# TX.net
KiCad netlist of a schematic drawn in Altium Designer
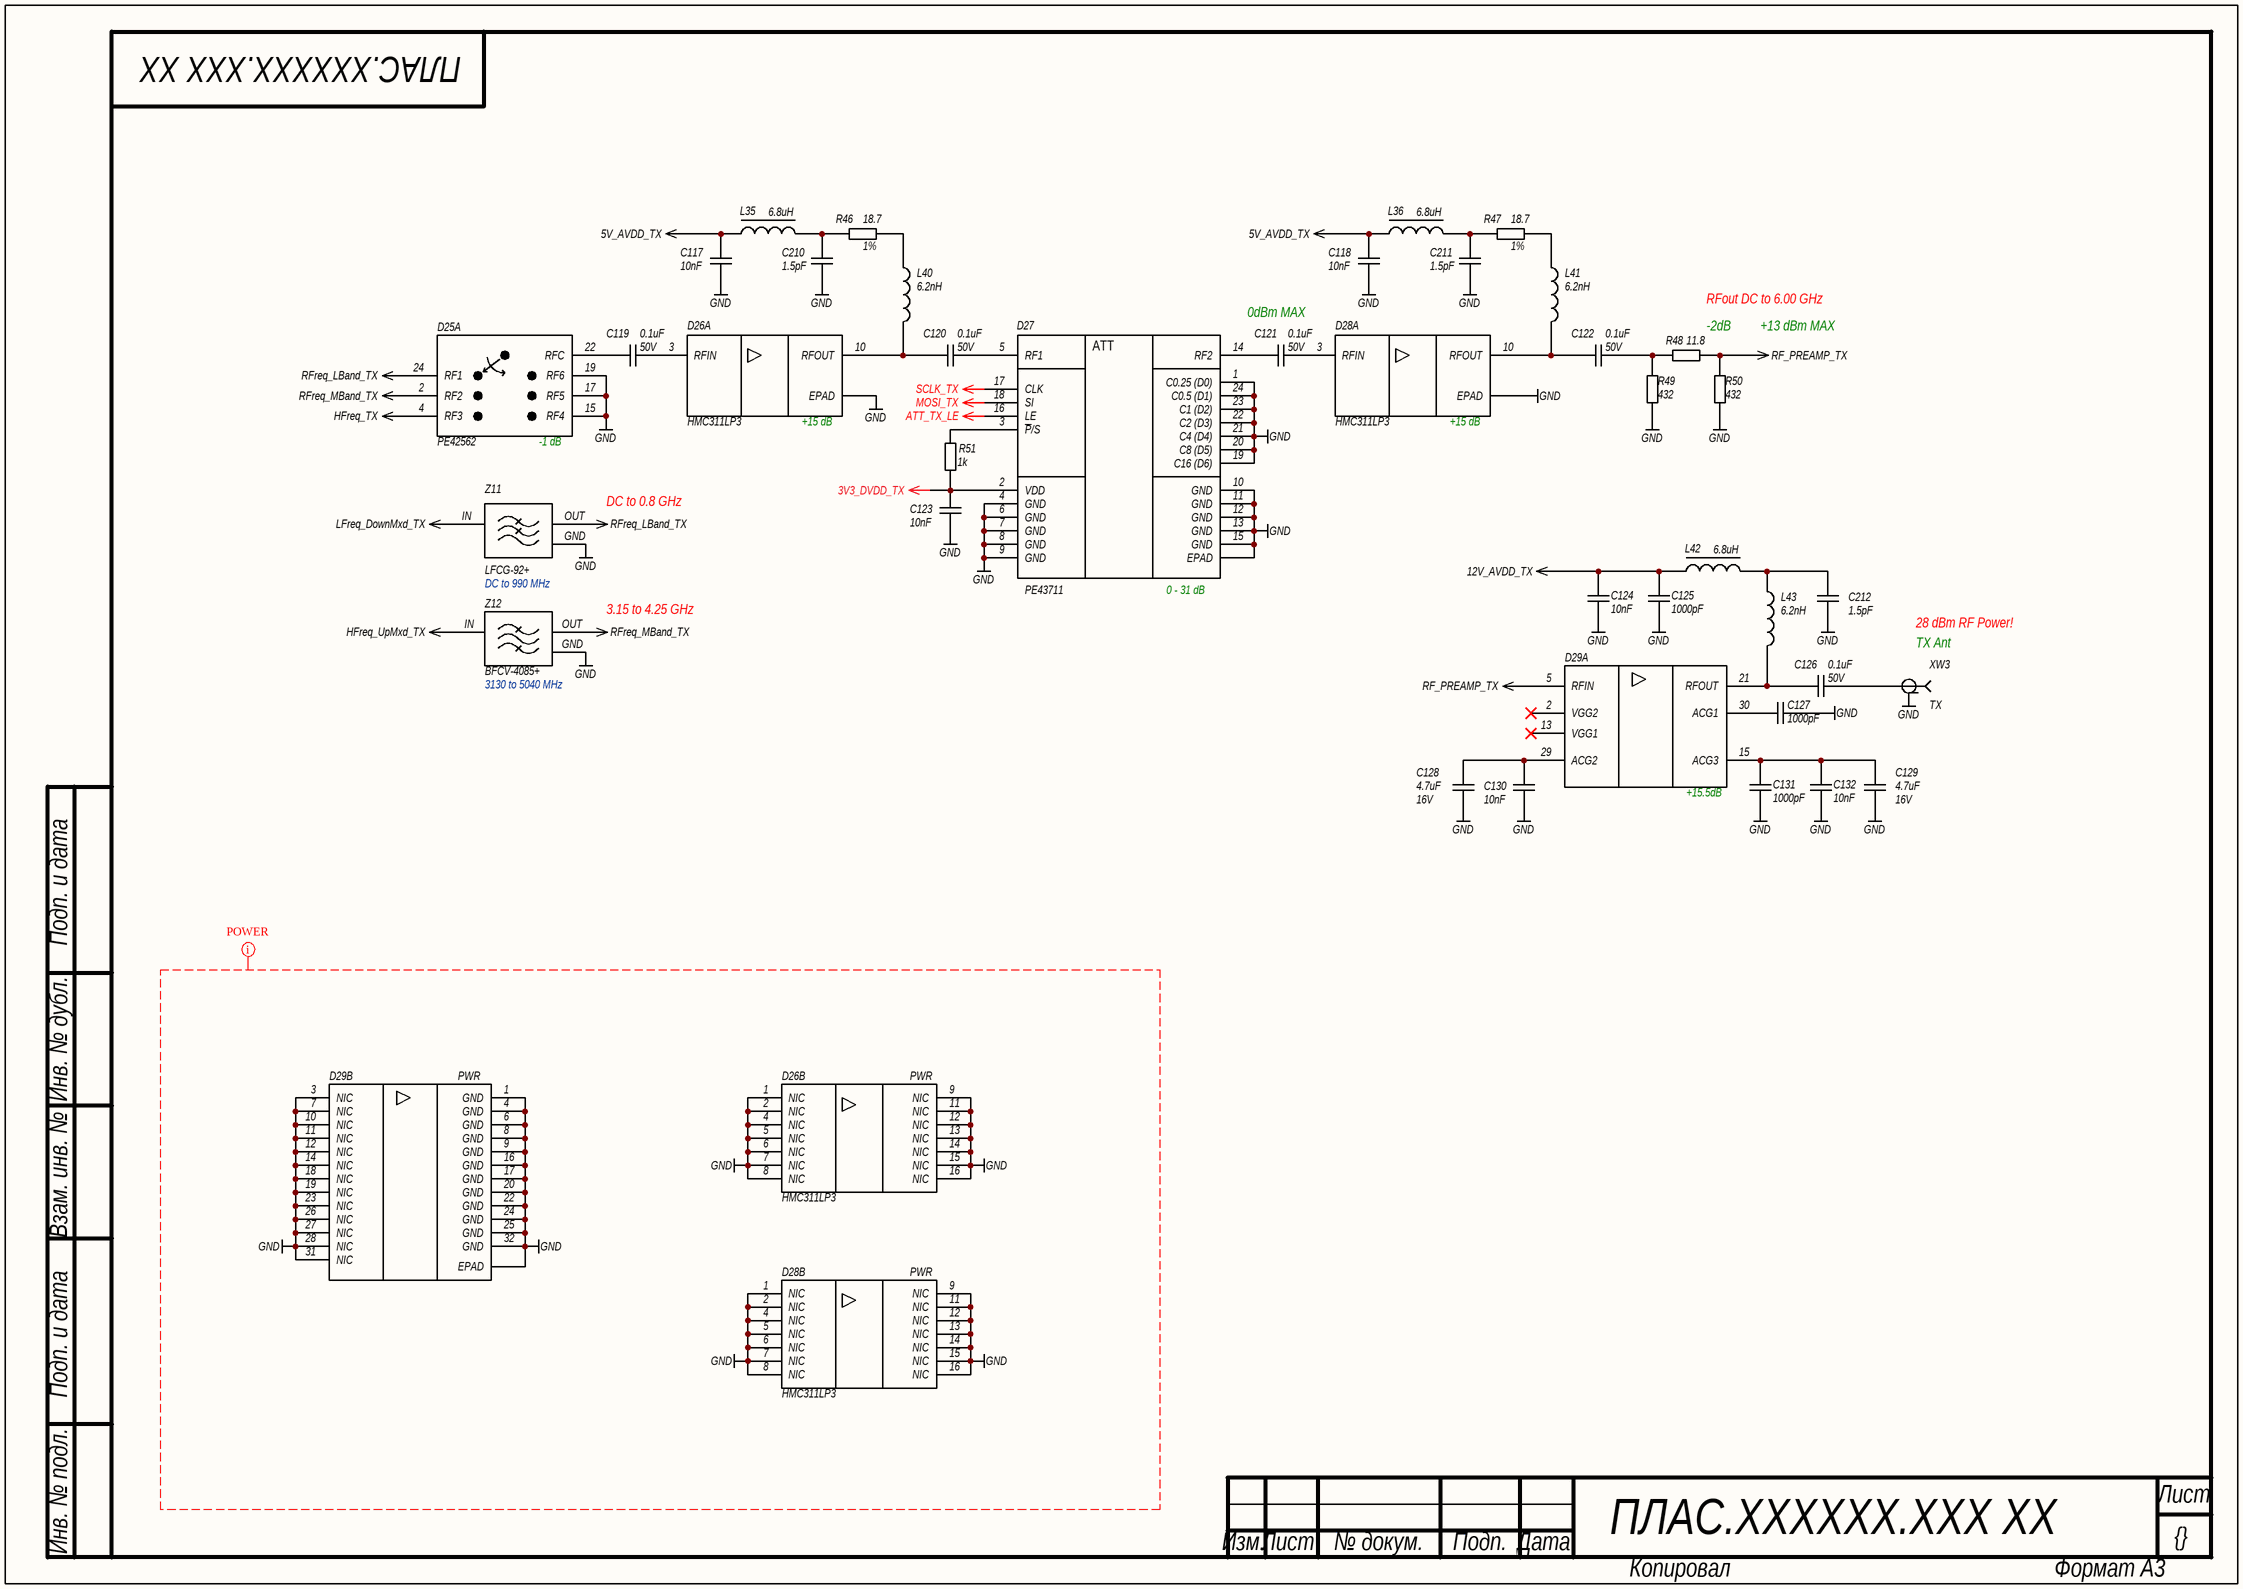
[diagram p0: TX.SchDoc]

(export (version "E")
  (design (tool "Eeschema 10.0.6"))
  (components
    (comp (ref "C117")
      (value "10nF")
      (footprint "C0402")
      (description "SMD Capacitor")
      (fields (field (name "MANUFACTURER") "Murata") (field (name "TOLERANCE") "10%"))
      (libsource (lib "Kintex_SDR") (part "CAP"))
    )
    (comp (ref "C118")
      (value "10nF")
      (footprint "C0402")
      (description "SMD Capacitor")
      (fields (field (name "MANUFACTURER") "Murata") (field (name "TOLERANCE") "10%"))
      (libsource (lib "Kintex_SDR") (part "CAP"))
    )
    (comp (ref "C119")
      (value "0.1uF")
      (footprint "C1206")
      (description "SMD Capacitor")
      (fields
        (field (name "MANUFACTURER") "Murata")
        (field (name "TOLERANCE") "5%")
        (field (name "VOLTAGE") "50V")
      )
      (libsource (lib "Kintex_SDR") (part "CAP"))
    )
    (comp (ref "C120")
      (value "0.1uF")
      (footprint "C1206")
      (description "SMD Capacitor")
      (fields
        (field (name "MANUFACTURER") "Murata")
        (field (name "TOLERANCE") "5%")
        (field (name "VOLTAGE") "50V")
      )
      (libsource (lib "Kintex_SDR") (part "CAP"))
    )
    (comp (ref "C121")
      (value "0.1uF")
      (footprint "C1206")
      (description "SMD Capacitor")
      (fields
        (field (name "MANUFACTURER") "Murata")
        (field (name "TOLERANCE") "5%")
        (field (name "VOLTAGE") "50V")
      )
      (libsource (lib "Kintex_SDR") (part "CAP"))
    )
    (comp (ref "C122")
      (value "0.1uF")
      (footprint "C1206")
      (description "SMD Capacitor")
      (fields
        (field (name "MANUFACTURER") "Murata")
        (field (name "TOLERANCE") "5%")
        (field (name "VOLTAGE") "50V")
      )
      (libsource (lib "Kintex_SDR") (part "CAP"))
    )
    (comp (ref "C123")
      (value "10nF")
      (footprint "C0402")
      (description "SMD Capacitor")
      (fields (field (name "MANUFACTURER") "Murata") (field (name "TOLERANCE") "10%"))
      (libsource (lib "Kintex_SDR") (part "CAP"))
    )
    (comp (ref "C124")
      (value "10nF")
      (footprint "C0402")
      (description "SMD Capacitor")
      (fields (field (name "MANUFACTURER") "Murata") (field (name "TOLERANCE") "10%"))
      (libsource (lib "Kintex_SDR") (part "CAP"))
    )
    (comp (ref "C125")
      (value "1000pF")
      (footprint "C0402")
      (description "SMD Capacitor")
      (fields (field (name "MANUFACTURER") "Murata") (field (name "TOLERANCE") "5%"))
      (libsource (lib "Kintex_SDR") (part "CAP"))
    )
    (comp (ref "C126")
      (value "0.1uF")
      (footprint "C1206")
      (description "SMD Capacitor")
      (fields
        (field (name "MANUFACTURER") "Murata")
        (field (name "TOLERANCE") "5%")
        (field (name "VOLTAGE") "50V")
      )
      (libsource (lib "Kintex_SDR") (part "CAP"))
    )
    (comp (ref "C127")
      (value "1000pF")
      (footprint "C0402")
      (description "SMD Capacitor")
      (fields (field (name "MANUFACTURER") "Murata") (field (name "TOLERANCE") "5%"))
      (libsource (lib "Kintex_SDR") (part "CAP"))
    )
    (comp (ref "C128")
      (value "4.7uF")
      (footprint "C0603")
      (description "SMD Capacitor")
      (fields
        (field (name "MANUFACTURER") "Murata")
        (field (name "TOLERANCE") "10%")
        (field (name "VOLTAGE") "16V")
      )
      (libsource (lib "Kintex_SDR") (part "CAP"))
    )
    (comp (ref "C129")
      (value "4.7uF")
      (footprint "C0603")
      (description "SMD Capacitor")
      (fields
        (field (name "MANUFACTURER") "Murata")
        (field (name "TOLERANCE") "10%")
        (field (name "VOLTAGE") "16V")
      )
      (libsource (lib "Kintex_SDR") (part "CAP"))
    )
    (comp (ref "C130")
      (value "10nF")
      (footprint "C0402")
      (description "SMD Capacitor")
      (fields (field (name "MANUFACTURER") "Murata") (field (name "TOLERANCE") "10%"))
      (libsource (lib "Kintex_SDR") (part "CAP"))
    )
    (comp (ref "C131")
      (value "1000pF")
      (footprint "C0402")
      (description "SMD Capacitor")
      (fields (field (name "MANUFACTURER") "Murata") (field (name "TOLERANCE") "5%"))
      (libsource (lib "Kintex_SDR") (part "CAP"))
    )
    (comp (ref "C132")
      (value "10nF")
      (footprint "C0402")
      (description "SMD Capacitor")
      (fields (field (name "MANUFACTURER") "Murata") (field (name "TOLERANCE") "10%"))
      (libsource (lib "Kintex_SDR") (part "CAP"))
    )
    (comp (ref "C210")
      (value "1.5pF")
      (footprint "C0402")
      (description "SMD Capacitor")
      (fields (field (name "MANUFACTURER") "Murata") (field (name "TOLERANCE") "±0.05pF"))
      (libsource (lib "Kintex_SDR") (part "CAP"))
    )
    (comp (ref "C211")
      (value "1.5pF")
      (footprint "C0402")
      (description "SMD Capacitor")
      (fields (field (name "MANUFACTURER") "Murata") (field (name "TOLERANCE") "±0.05pF"))
      (libsource (lib "Kintex_SDR") (part "CAP"))
    )
    (comp (ref "C212")
      (value "1.5pF")
      (footprint "C0402")
      (description "SMD Capacitor")
      (fields (field (name "MANUFACTURER") "Murata") (field (name "TOLERANCE") "±0.05pF"))
      (libsource (lib "Kintex_SDR") (part "CAP"))
    )
    (comp (ref "D25")
      (value "PE42562")
      (footprint "QFN-24")
      (description "The PE42582 is a HaRP™ technology-enhanced absorptive SP6T RF switch")
      (fields (field (name "MANUFACTURER") "Peregrine Technical Solutions"))
      (libsource (lib "DBLib") (part "PE42562"))
    )
    (comp (ref "D26")
      (value "HMC311LP3")
      (footprint "DBLib:QFN-16 v2")
      (description "InGaP HBT GAIN BLOCK")
      (fields (field (name "MANUFACTURER") "Analog Devices"))
      (libsource (lib "DBLib") (part "HMC311LP3"))
    )
    (comp (ref "D27")
      (value "PE43711")
      (footprint "QFN-24")
      (description "The PE43711 is a 50Ω, HaRP™ technology-enhanced, 7-bit RF digital step attenuator")
      (fields (field (name "MANUFACTURER") "Peregrine Technical Solutions"))
      (libsource (lib "DBLib") (part "PE43711"))
    )
    (comp (ref "D28")
      (value "HMC311LP3")
      (footprint "DBLib:QFN-16 v2")
      (description "InGaP HBT GAIN BLOCK")
      (fields (field (name "MANUFACTURER") "Analog Devices"))
      (libsource (lib "DBLib") (part "HMC311LP3"))
    )
    (comp (ref "D29")
      (value "HMC637BPM5E")
      (footprint "DBLib:LFCSP-32")
      (description "1 W Power Amplifier")
      (fields
        (field (name "MANUFACTURER") "Analog Devices")
        (field (name "VOLTAGE") "12 V at 345 mA typical")
      )
      (libsource (lib "DBLib") (part "HMC637BPM5E"))
    )
    (comp (ref "L35")
      (value "6.8uH")
      (footprint "DBLib:XFL3012")
      (description "Chip SMD Inductor")
      (fields (field (name "MANUFACTURER") "Coilcraft") (field (name "TOLERANCE") "±5%"))
      (libsource (lib "DBLib") (part "Inductor"))
    )
    (comp (ref "L36")
      (value "6.8uH")
      (footprint "DBLib:XFL3012")
      (description "Chip SMD Inductor")
      (fields (field (name "MANUFACTURER") "Coilcraft") (field (name "TOLERANCE") "±5%"))
      (libsource (lib "DBLib") (part "Inductor"))
    )
    (comp (ref "L40")
      (value "6.2nH")
      (footprint "DBLib:L0805_HP")
      (description "Chip SMD Inductor")
      (fields (field (name "MANUFACTURER") "Coilcraft") (field (name "TOLERANCE") "5%"))
      (libsource (lib "DBLib") (part "Inductor RF"))
    )
    (comp (ref "L41")
      (value "6.2nH")
      (footprint "DBLib:L0805_HP")
      (description "Chip SMD Inductor")
      (fields (field (name "MANUFACTURER") "Coilcraft") (field (name "TOLERANCE") "5%"))
      (libsource (lib "DBLib") (part "Inductor RF"))
    )
    (comp (ref "L42")
      (value "6.8uH")
      (footprint "DBLib:XFL3012")
      (description "Chip SMD Inductor")
      (fields (field (name "MANUFACTURER") "Coilcraft") (field (name "TOLERANCE") "±5%"))
      (libsource (lib "DBLib") (part "Inductor"))
    )
    (comp (ref "L43")
      (value "6.2nH")
      (footprint "DBLib:L0805_HP")
      (description "Chip SMD Inductor")
      (fields (field (name "MANUFACTURER") "Coilcraft") (field (name "TOLERANCE") "5%"))
      (libsource (lib "DBLib") (part "Inductor RF"))
    )
    (comp (ref "R46")
      (value "18.7")
      (footprint "R0805")
      (description "SMD Resistor")
      (fields
        (field (name "POWER") "0.125 Wt")
        (field (name "TOLERANCE") "1%")
        (field (name "MANUFACTURER") "Panasonic Electronic Components")
      )
      (libsource (lib "Kintex_SDR") (part "RES"))
    )
    (comp (ref "R47")
      (value "18.7")
      (footprint "R0805")
      (description "SMD Resistor")
      (fields
        (field (name "POWER") "0.125 Wt")
        (field (name "TOLERANCE") "1%")
        (field (name "MANUFACTURER") "Panasonic Electronic Components")
      )
      (libsource (lib "Kintex_SDR") (part "RES"))
    )
    (comp (ref "R48")
      (value "11.8")
      (footprint "R0402")
      (description "SMD Resistor")
      (fields (field (name "POWER") "0.063 Wt") (field (name "TOLERANCE") "±1%"))
      (libsource (lib "Kintex_SDR") (part "RES"))
    )
    (comp (ref "R49")
      (value "432")
      (footprint "R0402")
      (description "SMD Resistor")
      (fields (field (name "POWER") "0.1 Wt") (field (name "TOLERANCE") "±1%"))
      (libsource (lib "") (part "RES_1"))
    )
    (comp (ref "R50")
      (value "432")
      (footprint "R0402")
      (description "SMD Resistor")
      (fields (field (name "POWER") "0.1 Wt") (field (name "TOLERANCE") "±1%"))
      (libsource (lib "") (part "RES_1"))
    )
    (comp (ref "R51")
      (value "1k")
      (footprint "R0402")
      (description "SMD Resistor")
      (fields (field (name "POWER") "0.062 Wt") (field (name "TOLERANCE") "5%"))
      (libsource (lib "") (part "RES_2"))
    )
    (comp (ref "XW3")
      (value "TX")
      (footprint "MOLEX SD-73251-135 (Gold)")
      (description "50 Ohms, SMA Jack, Vertica")
      (fields (field (name "MANUFACTURER") "Molex"))
      (libsource (lib "DBLib") (part "RF Connector"))
    )
    (comp (ref "Z11")
      (value "LFCG-92+")
      (footprint "GE0805C-2")
      (description "Low Pass Filter")
      (fields (field (name "MANUFACTURER") "Mini-Circuits") (field (name "FREQUENCY") "DC to 990 MHz"))
      (libsource (lib "DBLib") (part "LFCG-92+"))
    )
    (comp (ref "Z12")
      (value "BFCV-4085+")
      (footprint "JV1210C")
      (description "Bandpass Filter")
      (fields (field (name "MANUFACTURER") "Mini-Circuits") (field (name "FREQUENCY") "3130 to 5040 MHz"))
      (libsource (lib "DBLib") (part "BFCV-4085+"))
    )
  )
  (nets
    (net (code "1") (name "3V3_DVDD_TX") (class "Default")
      (node (ref "C123") (pin "2") (pinfunction "2_2") (pintype "passive"))
      (node (ref "D27") (pin "2") (pinfunction "VDD_2") (pintype "passive"))
      (node (ref "R51") (pin "1") (pinfunction "1_1") (pintype "passive"))
    )
    (net (code "2") (name "5V_AVDD_TX") (class "Default")
      (node (ref "C117") (pin "2") (pinfunction "2_2") (pintype "passive"))
      (node (ref "C118") (pin "2") (pinfunction "2_2") (pintype "passive"))
      (node (ref "L35") (pin "1") (pinfunction "1_1") (pintype "passive"))
      (node (ref "L36") (pin "1") (pinfunction "1_1") (pintype "passive"))
    )
    (net (code "3") (name "12V_AVDD_TX") (class "Default")
      (node (ref "C124") (pin "2") (pinfunction "2_2") (pintype "passive"))
      (node (ref "C125") (pin "2") (pinfunction "2_2") (pintype "passive"))
      (node (ref "L42") (pin "1") (pinfunction "1_1") (pintype "passive"))
    )
    (net (code "4") (name "ATT_TX_LE") (class "Default")
      (node (ref "D27") (pin "16") (pinfunction "LE_16") (pintype "passive"))
    )
    (net (code "5") (name "GND") (class "Default")
      (node (ref "C117") (pin "1") (pinfunction "1_1") (pintype "passive"))
      (node (ref "C118") (pin "1") (pinfunction "1_1") (pintype "passive"))
      (node (ref "C123") (pin "1") (pinfunction "1_1") (pintype "passive"))
      (node (ref "C124") (pin "1") (pinfunction "1_1") (pintype "passive"))
      (node (ref "C125") (pin "1") (pinfunction "1_1") (pintype "passive"))
      (node (ref "C127") (pin "2") (pinfunction "2_2") (pintype "passive"))
      (node (ref "C128") (pin "2") (pinfunction "2_2") (pintype "passive"))
      (node (ref "C129") (pin "2") (pinfunction "2_2") (pintype "passive"))
      (node (ref "C130") (pin "1") (pinfunction "1_1") (pintype "passive"))
      (node (ref "C131") (pin "1") (pinfunction "1_1") (pintype "passive"))
      (node (ref "C132") (pin "1") (pinfunction "1_1") (pintype "passive"))
      (node (ref "C210") (pin "1") (pinfunction "1_1") (pintype "passive"))
      (node (ref "C211") (pin "1") (pinfunction "1_1") (pintype "passive"))
      (node (ref "C212") (pin "1") (pinfunction "1_1") (pintype "passive"))
      (node (ref "D25") (pin "15") (pinfunction "RF4_15") (pintype "passive"))
      (node (ref "D25") (pin "17") (pinfunction "RF5_17") (pintype "passive"))
      (node (ref "D25") (pin "19") (pinfunction "RF6_19") (pintype "passive"))
      (node (ref "D26") (pin "1") (pinfunction "NIC_1") (pintype "passive"))
      (node (ref "D26") (pin "11") (pinfunction "NIC_11") (pintype "passive"))
      (node (ref "D26") (pin "12") (pinfunction "NIC_12") (pintype "passive"))
      (node (ref "D26") (pin "13") (pinfunction "NIC_13") (pintype "passive"))
      (node (ref "D26") (pin "14") (pinfunction "NIC_14") (pintype "passive"))
      (node (ref "D26") (pin "15") (pinfunction "NIC_15") (pintype "passive"))
      (node (ref "D26") (pin "16") (pinfunction "NIC_16") (pintype "passive"))
      (node (ref "D26") (pin "17") (pinfunction "EPAD_17") (pintype "passive"))
      (node (ref "D26") (pin "2") (pinfunction "NIC_2") (pintype "passive"))
      (node (ref "D26") (pin "4") (pinfunction "NIC_4") (pintype "passive"))
      (node (ref "D26") (pin "5") (pinfunction "NIC_5") (pintype "passive"))
      (node (ref "D26") (pin "6") (pinfunction "NIC_6") (pintype "passive"))
      (node (ref "D26") (pin "7") (pinfunction "NIC_7") (pintype "passive"))
      (node (ref "D26") (pin "8") (pinfunction "NIC_8") (pintype "passive"))
      (node (ref "D26") (pin "9") (pinfunction "NIC_9") (pintype "passive"))
      (node (ref "D27") (pin "1") (pinfunction "C0.25_(D0)_1") (pintype "passive"))
      (node (ref "D27") (pin "10") (pinfunction "GND_10") (pintype "passive"))
      (node (ref "D27") (pin "11") (pinfunction "GND_11") (pintype "passive"))
      (node (ref "D27") (pin "12") (pinfunction "GND_12") (pintype "passive"))
      (node (ref "D27") (pin "13") (pinfunction "GND_13") (pintype "passive"))
      (node (ref "D27") (pin "15") (pinfunction "GND_15") (pintype "passive"))
      (node (ref "D27") (pin "19") (pinfunction "C16_(D6)_19") (pintype "passive"))
      (node (ref "D27") (pin "20") (pinfunction "C8_(D5)_20") (pintype "passive"))
      (node (ref "D27") (pin "21") (pinfunction "C4_(D4)_21") (pintype "passive"))
      (node (ref "D27") (pin "22") (pinfunction "C2_(D3)_22") (pintype "passive"))
      (node (ref "D27") (pin "23") (pinfunction "C1_(D2)_23") (pintype "passive"))
      (node (ref "D27") (pin "24") (pinfunction "C0.5_(D1)_24") (pintype "passive"))
      (node (ref "D27") (pin "25") (pinfunction "EPAD_25") (pintype "passive"))
      (node (ref "D27") (pin "4") (pinfunction "GND_4") (pintype "passive"))
      (node (ref "D27") (pin "6") (pinfunction "GND_6") (pintype "passive"))
      (node (ref "D27") (pin "7") (pinfunction "GND_7") (pintype "passive"))
      (node (ref "D27") (pin "8") (pinfunction "GND_8") (pintype "passive"))
      (node (ref "D27") (pin "9") (pinfunction "GND_9") (pintype "passive"))
      (node (ref "D28") (pin "1") (pinfunction "NIC_1") (pintype "passive"))
      (node (ref "D28") (pin "11") (pinfunction "NIC_11") (pintype "passive"))
      (node (ref "D28") (pin "12") (pinfunction "NIC_12") (pintype "passive"))
      (node (ref "D28") (pin "13") (pinfunction "NIC_13") (pintype "passive"))
      (node (ref "D28") (pin "14") (pinfunction "NIC_14") (pintype "passive"))
      (node (ref "D28") (pin "15") (pinfunction "NIC_15") (pintype "passive"))
      (node (ref "D28") (pin "16") (pinfunction "NIC_16") (pintype "passive"))
      (node (ref "D28") (pin "17") (pinfunction "EPAD_17") (pintype "passive"))
      (node (ref "D28") (pin "2") (pinfunction "NIC_2") (pintype "passive"))
      (node (ref "D28") (pin "4") (pinfunction "NIC_4") (pintype "passive"))
      (node (ref "D28") (pin "5") (pinfunction "NIC_5") (pintype "passive"))
      (node (ref "D28") (pin "6") (pinfunction "NIC_6") (pintype "passive"))
      (node (ref "D28") (pin "7") (pinfunction "NIC_7") (pintype "passive"))
      (node (ref "D28") (pin "8") (pinfunction "NIC_8") (pintype "passive"))
      (node (ref "D28") (pin "9") (pinfunction "NIC_9") (pintype "passive"))
      (node (ref "D29") (pin "0") (pinfunction "EPAD_0") (pintype "passive"))
      (node (ref "D29") (pin "1") (pinfunction "GND_1") (pintype "passive"))
      (node (ref "D29") (pin "10") (pinfunction "NIC_10") (pintype "passive"))
      (node (ref "D29") (pin "11") (pinfunction "NIC_11") (pintype "passive"))
      (node (ref "D29") (pin "12") (pinfunction "NIC_12") (pintype "passive"))
      (node (ref "D29") (pin "14") (pinfunction "NIC_14") (pintype "passive"))
      (node (ref "D29") (pin "16") (pinfunction "GND_16") (pintype "passive"))
      (node (ref "D29") (pin "17") (pinfunction "GND_17") (pintype "passive"))
      (node (ref "D29") (pin "18") (pinfunction "NIC_18") (pintype "passive"))
      (node (ref "D29") (pin "19") (pinfunction "NIC_19") (pintype "passive"))
      (node (ref "D29") (pin "20") (pinfunction "GND_20") (pintype "passive"))
      (node (ref "D29") (pin "22") (pinfunction "GND_22") (pintype "passive"))
      (node (ref "D29") (pin "23") (pinfunction "NIC_23") (pintype "passive"))
      (node (ref "D29") (pin "24") (pinfunction "GND_24") (pintype "passive"))
      (node (ref "D29") (pin "25") (pinfunction "GND_25") (pintype "passive"))
      (node (ref "D29") (pin "26") (pinfunction "NIC_26") (pintype "passive"))
      (node (ref "D29") (pin "27") (pinfunction "NIC_27") (pintype "passive"))
      (node (ref "D29") (pin "28") (pinfunction "NIC_28") (pintype "passive"))
      (node (ref "D29") (pin "3") (pinfunction "NIC_3") (pintype "passive"))
      (node (ref "D29") (pin "31") (pinfunction "NIC_31") (pintype "passive"))
      (node (ref "D29") (pin "32") (pinfunction "GND_32") (pintype "passive"))
      (node (ref "D29") (pin "4") (pinfunction "GND_4") (pintype "passive"))
      (node (ref "D29") (pin "6") (pinfunction "GND_6") (pintype "passive"))
      (node (ref "D29") (pin "7") (pinfunction "NIC_7") (pintype "passive"))
      (node (ref "D29") (pin "8") (pinfunction "GND_8") (pintype "passive"))
      (node (ref "D29") (pin "9") (pinfunction "GND_9") (pintype "passive"))
      (node (ref "R49") (pin "2") (pinfunction "2_2") (pintype "passive"))
      (node (ref "R50") (pin "2") (pinfunction "2_2") (pintype "passive"))
      (node (ref "XW3") (pin "G") (pinfunction "GND_G") (pintype "passive"))
      (node (ref "Z11") (pin "GND") (pinfunction "GND_GND") (pintype "passive"))
      (node (ref "Z12") (pin "GND") (pinfunction "GND_GND") (pintype "passive"))
    )
    (net (code "6") (name "HFreq_TX") (class "Default")
      (node (ref "D25") (pin "4") (pinfunction "RF3_4") (pintype "passive"))
    )
    (net (code "7") (name "HFreq_UpMxd_TX") (class "Default")
      (node (ref "Z12") (pin "IN") (pinfunction "IN_IN") (pintype "passive"))
    )
    (net (code "8") (name "LFreq_DownMxd_TX") (class "Default")
      (node (ref "Z11") (pin "IN") (pinfunction "IN_IN") (pintype "passive"))
    )
    (net (code "9") (name "MOSI_TX") (class "Default")
      (node (ref "D27") (pin "18") (pinfunction "SI_18") (pintype "passive"))
    )
    (net (code "10") (name "Net-(C122-Pad1)") (class "Default")
      (node (ref "C122") (pin "1") (pinfunction "1_1") (pintype "passive"))
      (node (ref "R48") (pin "2") (pinfunction "2_2") (pintype "passive"))
      (node (ref "R49") (pin "1") (pinfunction "1_1") (pintype "passive"))
    )
    (net (code "11") (name "Net-(C210-Pad2)") (class "Default")
      (node (ref "C210") (pin "2") (pinfunction "2_2") (pintype "passive"))
      (node (ref "L35") (pin "2") (pinfunction "2_2") (pintype "passive"))
      (node (ref "R46") (pin "2") (pinfunction "2_2") (pintype "passive"))
    )
    (net (code "12") (name "Net-(C211-Pad2)") (class "Default")
      (node (ref "C211") (pin "2") (pinfunction "2_2") (pintype "passive"))
      (node (ref "L36") (pin "2") (pinfunction "2_2") (pintype "passive"))
      (node (ref "R47") (pin "2") (pinfunction "2_2") (pintype "passive"))
    )
    (net (code "13") (name "Net-(C212-Pad2)") (class "Default")
      (node (ref "C212") (pin "2") (pinfunction "2_2") (pintype "passive"))
      (node (ref "L42") (pin "2") (pinfunction "2_2") (pintype "passive"))
      (node (ref "L43") (pin "2") (pinfunction "2_2") (pintype "passive"))
    )
    (net (code "14") (name "Net-(D25A-RFC)") (class "Default")
      (node (ref "C119") (pin "2") (pinfunction "2_2") (pintype "passive"))
      (node (ref "D25") (pin "22") (pinfunction "RFC_22") (pintype "passive"))
    )
    (net (code "15") (name "Net-(D26A-RFIN)") (class "Default")
      (node (ref "C119") (pin "1") (pinfunction "1_1") (pintype "passive"))
      (node (ref "D26") (pin "3") (pinfunction "RFIN_3") (pintype "passive"))
    )
    (net (code "16") (name "Net-(D26A-RFOUT)") (class "Default")
      (node (ref "C120") (pin "2") (pinfunction "2_2") (pintype "passive"))
      (node (ref "D26") (pin "10") (pinfunction "RFOUT_10") (pintype "passive"))
      (node (ref "L40") (pin "1") (pinfunction "1_1") (pintype "passive"))
    )
    (net (code "17") (name "Net-(D27-RF1)") (class "Default")
      (node (ref "C120") (pin "1") (pinfunction "1_1") (pintype "passive"))
      (node (ref "D27") (pin "5") (pinfunction "RF1_5") (pintype "passive"))
    )
    (net (code "18") (name "Net-(D27-RF2)") (class "Default")
      (node (ref "C121") (pin "2") (pinfunction "2_2") (pintype "passive"))
      (node (ref "D27") (pin "14") (pinfunction "RF2_14") (pintype "passive"))
    )
    (net (code "19") (name "Net-(D27-~{P}{slash}S)") (class "Default")
      (node (ref "D27") (pin "3") (pinfunction "~{P}/S_3") (pintype "passive"))
      (node (ref "R51") (pin "2") (pinfunction "2_2") (pintype "passive"))
    )
    (net (code "20") (name "Net-(D28A-RFIN)") (class "Default")
      (node (ref "C121") (pin "1") (pinfunction "1_1") (pintype "passive"))
      (node (ref "D28") (pin "3") (pinfunction "RFIN_3") (pintype "passive"))
    )
    (net (code "21") (name "Net-(D28A-RFOUT)") (class "Default")
      (node (ref "C122") (pin "2") (pinfunction "2_2") (pintype "passive"))
      (node (ref "D28") (pin "10") (pinfunction "RFOUT_10") (pintype "passive"))
      (node (ref "L41") (pin "1") (pinfunction "1_1") (pintype "passive"))
    )
    (net (code "22") (name "Net-(D29A-ACG1)") (class "Default")
      (node (ref "C127") (pin "1") (pinfunction "1_1") (pintype "passive"))
      (node (ref "D29") (pin "30") (pinfunction "ACG1_30") (pintype "passive"))
    )
    (net (code "23") (name "Net-(D29A-ACG2)") (class "Default")
      (node (ref "C128") (pin "1") (pinfunction "1_1") (pintype "passive"))
      (node (ref "C130") (pin "2") (pinfunction "2_2") (pintype "passive"))
      (node (ref "D29") (pin "29") (pinfunction "ACG2_29") (pintype "passive"))
    )
    (net (code "24") (name "Net-(D29A-ACG3)") (class "Default")
      (node (ref "C129") (pin "1") (pinfunction "1_1") (pintype "passive"))
      (node (ref "C131") (pin "2") (pinfunction "2_2") (pintype "passive"))
      (node (ref "C132") (pin "2") (pinfunction "2_2") (pintype "passive"))
      (node (ref "D29") (pin "15") (pinfunction "ACG3_15") (pintype "passive"))
    )
    (net (code "25") (name "Net-(D29A-RFOUT)") (class "Default")
      (node (ref "C126") (pin "2") (pinfunction "2_2") (pintype "passive"))
      (node (ref "D29") (pin "21") (pinfunction "RFOUT_21") (pintype "passive"))
      (node (ref "L43") (pin "1") (pinfunction "1_1") (pintype "passive"))
    )
    (net (code "26") (name "Net-(L40-Pad2)") (class "Default")
      (node (ref "L40") (pin "2") (pinfunction "2_2") (pintype "passive"))
      (node (ref "R46") (pin "1") (pinfunction "1_1") (pintype "passive"))
    )
    (net (code "27") (name "Net-(L41-Pad2)") (class "Default")
      (node (ref "L41") (pin "2") (pinfunction "2_2") (pintype "passive"))
      (node (ref "R47") (pin "1") (pinfunction "1_1") (pintype "passive"))
    )
    (net (code "28") (name "Net-(XW3-RF)") (class "Default")
      (node (ref "C126") (pin "1") (pinfunction "1_1") (pintype "passive"))
      (node (ref "XW3") (pin "S") (pinfunction "RF_S") (pintype "passive"))
    )
    (net (code "29") (name "RF_PREAMP_TX") (class "Default")
      (node (ref "D29") (pin "5") (pinfunction "RFIN_5") (pintype "passive"))
      (node (ref "R48") (pin "1") (pinfunction "1_1") (pintype "passive"))
      (node (ref "R50") (pin "1") (pinfunction "1_1") (pintype "passive"))
    )
    (net (code "30") (name "RFreq_LBand_TX") (class "Default")
      (node (ref "D25") (pin "24") (pinfunction "RF1_24") (pintype "passive"))
      (node (ref "Z11") (pin "OUT") (pinfunction "OUT_OUT") (pintype "passive"))
    )
    (net (code "31") (name "RFreq_MBand_TX") (class "Default")
      (node (ref "D25") (pin "2") (pinfunction "RF2_2") (pintype "passive"))
      (node (ref "Z12") (pin "OUT") (pinfunction "OUT_OUT") (pintype "passive"))
    )
    (net (code "32") (name "SCLK_TX") (class "Default")
      (node (ref "D27") (pin "17") (pinfunction "CLK_17") (pintype "passive"))
    )
    (net (code "33") (name "unconnected-(D29A-VGG1-Pad13)") (class "Default")
      (node (ref "D29") (pin "13") (pinfunction "VGG1_13") (pintype "passive+no_connect"))
    )
    (net (code "34") (name "unconnected-(D29A-VGG2-Pad2)") (class "Default")
      (node (ref "D29") (pin "2") (pinfunction "VGG2_2") (pintype "passive+no_connect"))
    )
  )
)
